# ECU.net
KiCad netlist of a schematic drawn in EAGLE
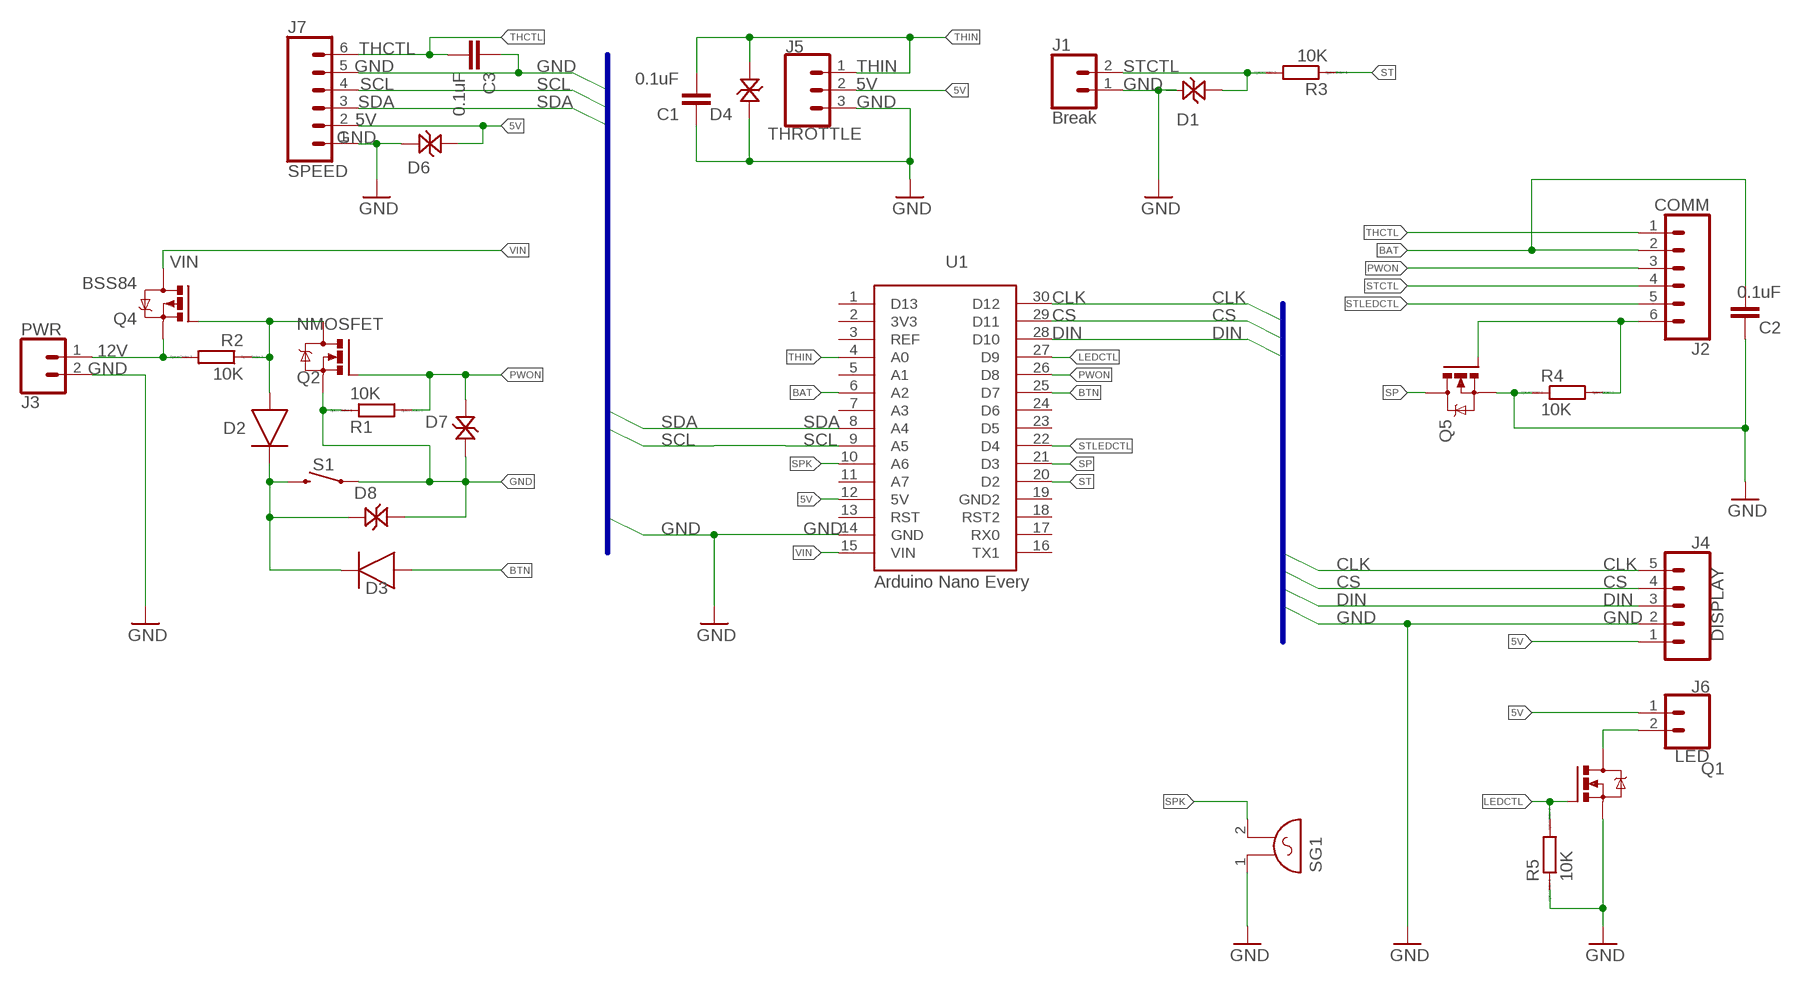
[diagram p0: schematic, sheet 1]

(export (version "E")
  (design (tool "Eeschema 10.0.6"))
  (components
    (comp (ref "C1")
      (value "0.1uF")
      (footprint "eagle-import:CAPC3216X135")
      (libsource (lib "eagle-import") (part "CCHIP-1206(3216-METRIC)_"))
    )
    (comp (ref "C2")
      (value "0.1uF")
      (footprint "eagle-import:CAPC3216X135")
      (libsource (lib "eagle-import") (part "CCHIP-1206(3216-METRIC)_"))
    )
    (comp (ref "C3")
      (value "0.1uF")
      (footprint "eagle-import:CAPC3216X135")
      (libsource (lib "eagle-import") (part "CCHIP-1206(3216-METRIC)_"))
    )
    (comp (ref "D1")
      (value "TVS_DIODESMA")
      (footprint "eagle-import:DIOM5027X220N")
      (libsource (lib "eagle-import") (part "TVS_DIODESMA"))
    )
    (comp (ref "D2")
      (value "DIODE_DO-215-AC")
      (footprint "eagle-import:SOD6126X290")
      (libsource (lib "eagle-import") (part "DIODEDO-215-AC_"))
    )
    (comp (ref "D3")
      (value "DIODE_DO-215-AC")
      (footprint "eagle-import:SOD6126X290")
      (libsource (lib "eagle-import") (part "DIODEDO-215-AC_"))
    )
    (comp (ref "D4")
      (value "TVS_DIODESMA")
      (footprint "eagle-import:DIOM5027X220N")
      (libsource (lib "eagle-import") (part "TVS_DIODESMA"))
    )
    (comp (ref "D6")
      (value "TVS_DIODESMA")
      (footprint "eagle-import:DIOM5027X220N")
      (libsource (lib "eagle-import") (part "TVS_DIODESMA"))
    )
    (comp (ref "D7")
      (value "TVS_DIODESMA")
      (footprint "eagle-import:DIOM5027X220N")
      (libsource (lib "eagle-import") (part "TVS_DIODESMA"))
    )
    (comp (ref "D8")
      (value "TVS_DIODESMA")
      (footprint "eagle-import:DIOM5027X220N")
      (libsource (lib "eagle-import") (part "TVS_DIODESMA"))
    )
    (comp (ref "J1")
      (value "Break")
      (footprint "eagle-import:1X02")
      (libsource (lib "eagle-import") (part "CONN_02"))
    )
    (comp (ref "J2")
      (value "COMM")
      (footprint "eagle-import:1X06")
      (libsource (lib "eagle-import") (part "CONN_06SILK_FEMALE_PTH"))
    )
    (comp (ref "J3")
      (value "PWR")
      (footprint "eagle-import:1X02")
      (libsource (lib "eagle-import") (part "CONN_02"))
    )
    (comp (ref "J4")
      (value "DISPLAY")
      (footprint "eagle-import:1X05")
      (libsource (lib "eagle-import") (part "CONN_05"))
    )
    (comp (ref "J5")
      (value "THROTTLE")
      (footprint "eagle-import:1X03")
      (libsource (lib "eagle-import") (part "CONN_03"))
    )
    (comp (ref "J6")
      (value "LED")
      (footprint "eagle-import:1X02")
      (libsource (lib "eagle-import") (part "CONN_02"))
    )
    (comp (ref "J7")
      (value "SPEED")
      (footprint "eagle-import:1X06")
      (libsource (lib "eagle-import") (part "CONN_06SILK_FEMALE_PTH"))
    )
    (comp (ref "Q1")
      (value "NMOSFET")
      (footprint "eagle-import:SOT23")
      (libsource (lib "eagle-import") (part "NMOSFETSOT23"))
    )
    (comp (ref "Q2")
      (value "NMOSFET")
      (footprint "eagle-import:SOT23")
      (libsource (lib "eagle-import") (part "NMOSFETSOT23"))
    )
    (comp (ref "Q4")
      (value "BSS84")
      (footprint "eagle-import:SOT23")
      (fields (field (name "MANUFACTURER") "ON Semiconductor"))
      (libsource (lib "eagle-import") (part "PMOSFET_BSS84"))
    )
    (comp (ref "Q5")
      (value "NMOSFET")
      (footprint "eagle-import:SOT23")
      (libsource (lib "eagle-import") (part "NMOSFETSOT23"))
    )
    (comp (ref "R1")
      (value "10K")
      (footprint "eagle-import:R1206")
      (libsource (lib "eagle-import") (part "RR1206"))
    )
    (comp (ref "R2")
      (value "10K")
      (footprint "eagle-import:R1206")
      (libsource (lib "eagle-import") (part "RR1206"))
    )
    (comp (ref "R3")
      (value "10K")
      (footprint "eagle-import:R1206")
      (libsource (lib "eagle-import") (part "RR1206"))
    )
    (comp (ref "R4")
      (value "10K")
      (footprint "eagle-import:R1206")
      (libsource (lib "eagle-import") (part "RR1206"))
    )
    (comp (ref "R5")
      (value "10K")
      (footprint "eagle-import:R1206")
      (libsource (lib "eagle-import") (part "RR1206"))
    )
    (comp (ref "S1")
      (value "MOMENTARY-SWITCH-SPST-PTH-6.0MM")
      (footprint "eagle-import:TACTILE_SWITCH_PTH_6.0MM")
      (libsource (lib "eagle-import") (part "MOMENTARY-SWITCH-SPST-PTH-6.0MM"))
    )
    (comp (ref "SG1")
      (value "F/HGP")
      (footprint "eagle-import:F_HGP")
      (libsource (lib "eagle-import") (part "F/HGP"))
    )
    (comp (ref "U1")
      (value "Arduino Nano Every")
      (footprint "eagle-import:SON254P1750X4300X120-30M")
      (libsource (lib "eagle-import") (part "ARDUINOARDUINO_NANO"))
    )
  )
  (nets
    (net (code "1") (name "/3V3") (class "Default")
      (node (ref "U1") (pin "2") (pinfunction "3V3_2") (pintype "power_in"))
    )
    (net (code "2") (name "/12V") (class "Default")
      (node (ref "J3") (pin "1") (pinfunction "1_1") (pintype "passive"))
      (node (ref "Q4") (pin "2") (pinfunction "S_2") (pintype "passive"))
      (node (ref "R2") (pin "2") (pinfunction "2_2") (pintype "passive"))
    )
    (net (code "3") (name "/CLK") (class "Default")
      (node (ref "J4") (pin "5") (pinfunction "5_5") (pintype "passive"))
      (node (ref "U1") (pin "30") (pinfunction "D12_30") (pintype "bidirectional"))
    )
    (net (code "4") (name "/CS") (class "Default")
      (node (ref "J4") (pin "4") (pinfunction "4_4") (pintype "passive"))
      (node (ref "U1") (pin "29") (pinfunction "D11_29") (pintype "bidirectional"))
    )
    (net (code "5") (name "/DIN") (class "Default")
      (node (ref "J4") (pin "3") (pinfunction "3_3") (pintype "passive"))
      (node (ref "U1") (pin "28") (pinfunction "D10_28") (pintype "bidirectional"))
    )
    (net (code "6") (name "/GND2") (class "Default")
      (node (ref "U1") (pin "19") (pinfunction "GND2_19") (pintype "power_in"))
    )
    (net (code "7") (name "/SCL") (class "Default")
      (node (ref "J7") (pin "4") (pinfunction "4_4") (pintype "passive"))
      (node (ref "U1") (pin "9") (pinfunction "A5_9") (pintype "bidirectional"))
    )
    (net (code "8") (name "/SDA") (class "Default")
      (node (ref "J7") (pin "3") (pinfunction "3_3") (pintype "passive"))
      (node (ref "U1") (pin "8") (pinfunction "A4_8") (pintype "bidirectional"))
    )
    (net (code "9") (name "5V") (class "Default")
      (node (ref "D6") (pin "1") (pinfunction "P$1_1") (pintype "bidirectional"))
      (node (ref "J4") (pin "1") (pinfunction "1_1") (pintype "passive"))
      (node (ref "J5") (pin "2") (pinfunction "2_2") (pintype "passive"))
      (node (ref "J6") (pin "1") (pinfunction "1_1") (pintype "passive"))
      (node (ref "J7") (pin "2") (pinfunction "2_2") (pintype "passive"))
      (node (ref "U1") (pin "12") (pinfunction "5V_12") (pintype "power_in"))
    )
    (net (code "10") (name "BAT") (class "Default")
      (node (ref "C2") (pin "1") (pinfunction "1_1") (pintype "passive"))
      (node (ref "J2") (pin "2") (pinfunction "2_2") (pintype "passive"))
      (node (ref "U1") (pin "6") (pinfunction "A2_6") (pintype "bidirectional"))
    )
    (net (code "11") (name "BTN") (class "Default")
      (node (ref "D3") (pin "2") (pinfunction "A_2") (pintype "passive"))
      (node (ref "U1") (pin "25") (pinfunction "D7_25") (pintype "bidirectional"))
    )
    (net (code "12") (name "GND") (class "Default")
      (node (ref "C1") (pin "1") (pinfunction "1_1") (pintype "passive"))
      (node (ref "C2") (pin "2") (pinfunction "2_2") (pintype "passive"))
      (node (ref "C3") (pin "2") (pinfunction "2_2") (pintype "passive"))
      (node (ref "D1") (pin "1") (pinfunction "P$1_1") (pintype "bidirectional"))
      (node (ref "D4") (pin "1") (pinfunction "P$1_1") (pintype "bidirectional"))
      (node (ref "D6") (pin "2") (pinfunction "P$2_2") (pintype "bidirectional"))
      (node (ref "D7") (pin "2") (pinfunction "P$2_2") (pintype "bidirectional"))
      (node (ref "D8") (pin "1") (pinfunction "P$1_1") (pintype "bidirectional"))
      (node (ref "J1") (pin "1") (pinfunction "1_1") (pintype "passive"))
      (node (ref "J3") (pin "2") (pinfunction "2_2") (pintype "passive"))
      (node (ref "J4") (pin "2") (pinfunction "2_2") (pintype "passive"))
      (node (ref "J5") (pin "3") (pinfunction "3_3") (pintype "passive"))
      (node (ref "J7") (pin "1") (pinfunction "1_1") (pintype "passive"))
      (node (ref "J7") (pin "5") (pinfunction "5_5") (pintype "passive"))
      (node (ref "Q1") (pin "2") (pinfunction "S_2") (pintype "passive"))
      (node (ref "Q2") (pin "2") (pinfunction "S_2") (pintype "passive"))
      (node (ref "Q5") (pin "2") (pinfunction "S_2") (pintype "passive"))
      (node (ref "R1") (pin "1") (pinfunction "1_1") (pintype "passive"))
      (node (ref "R4") (pin "1") (pinfunction "1_1") (pintype "passive"))
      (node (ref "R5") (pin "1") (pinfunction "1_1") (pintype "passive"))
      (node (ref "S1") (pin "1") (pinfunction "1_1") (pintype "passive"))
      (node (ref "S1") (pin "2") (pinfunction "1_2") (pintype "passive"))
      (node (ref "SG1") (pin "1") (pinfunction "1_1") (pintype "passive"))
      (node (ref "U1") (pin "14") (pinfunction "GND_14") (pintype "power_in"))
    )
    (net (code "13") (name "LEDCTL") (class "Default")
      (node (ref "Q1") (pin "1") (pinfunction "G_1") (pintype "passive"))
      (node (ref "R5") (pin "2") (pinfunction "2_2") (pintype "passive"))
      (node (ref "U1") (pin "27") (pinfunction "D9_27") (pintype "bidirectional"))
    )
    (net (code "14") (name "Net-(D2-A)") (class "Default")
      (node (ref "D2") (pin "2") (pinfunction "A_2") (pintype "passive"))
      (node (ref "Q2") (pin "3") (pinfunction "D_3") (pintype "passive"))
      (node (ref "Q4") (pin "1") (pinfunction "G_1") (pintype "passive"))
      (node (ref "R2") (pin "1") (pinfunction "1_1") (pintype "passive"))
    )
    (net (code "15") (name "Net-(D2-C)") (class "Default")
      (node (ref "D2") (pin "1") (pinfunction "C_1") (pintype "passive"))
      (node (ref "D3") (pin "1") (pinfunction "C_1") (pintype "passive"))
      (node (ref "D8") (pin "2") (pinfunction "P$2_2") (pintype "bidirectional"))
      (node (ref "S1") (pin "3") (pinfunction "2_3") (pintype "passive"))
      (node (ref "S1") (pin "4") (pinfunction "2_4") (pintype "passive"))
    )
    (net (code "16") (name "Net-(Q1-D)") (class "Default")
      (node (ref "J6") (pin "2") (pinfunction "2_2") (pintype "passive"))
      (node (ref "Q1") (pin "3") (pinfunction "D_3") (pintype "passive"))
    )
    (net (code "17") (name "Net-(Q5-G)") (class "Default")
      (node (ref "J2") (pin "6") (pinfunction "6_6") (pintype "passive"))
      (node (ref "Q5") (pin "1") (pinfunction "G_1") (pintype "passive"))
      (node (ref "R4") (pin "2") (pinfunction "2_2") (pintype "passive"))
    )
    (net (code "18") (name "PWON") (class "Default")
      (node (ref "D7") (pin "1") (pinfunction "P$1_1") (pintype "bidirectional"))
      (node (ref "J2") (pin "3") (pinfunction "3_3") (pintype "passive"))
      (node (ref "Q2") (pin "1") (pinfunction "G_1") (pintype "passive"))
      (node (ref "R1") (pin "2") (pinfunction "2_2") (pintype "passive"))
      (node (ref "U1") (pin "26") (pinfunction "D8_26") (pintype "bidirectional"))
    )
    (net (code "19") (name "SP") (class "Default")
      (node (ref "Q5") (pin "3") (pinfunction "D_3") (pintype "passive"))
      (node (ref "U1") (pin "21") (pinfunction "D3_21") (pintype "bidirectional"))
    )
    (net (code "20") (name "SPK") (class "Default")
      (node (ref "SG1") (pin "2") (pinfunction "2_2") (pintype "passive"))
      (node (ref "U1") (pin "10") (pinfunction "A6_10") (pintype "bidirectional"))
    )
    (net (code "21") (name "ST") (class "Default")
      (node (ref "R3") (pin "1") (pinfunction "1_1") (pintype "passive"))
      (node (ref "U1") (pin "20") (pinfunction "D2_20") (pintype "bidirectional"))
    )
    (net (code "22") (name "STCTL") (class "Default")
      (node (ref "D1") (pin "2") (pinfunction "P$2_2") (pintype "bidirectional"))
      (node (ref "J1") (pin "2") (pinfunction "2_2") (pintype "passive"))
      (node (ref "J2") (pin "4") (pinfunction "4_4") (pintype "passive"))
      (node (ref "R3") (pin "2") (pinfunction "2_2") (pintype "passive"))
    )
    (net (code "23") (name "STLEDCTL") (class "Default")
      (node (ref "J2") (pin "5") (pinfunction "5_5") (pintype "passive"))
      (node (ref "U1") (pin "22") (pinfunction "D4_22") (pintype "bidirectional"))
    )
    (net (code "24") (name "THCTL") (class "Default")
      (node (ref "C3") (pin "1") (pinfunction "1_1") (pintype "passive"))
      (node (ref "J2") (pin "1") (pinfunction "1_1") (pintype "passive"))
      (node (ref "J7") (pin "6") (pinfunction "6_6") (pintype "passive"))
    )
    (net (code "25") (name "THIN") (class "Default")
      (node (ref "C1") (pin "2") (pinfunction "2_2") (pintype "passive"))
      (node (ref "D4") (pin "2") (pinfunction "P$2_2") (pintype "bidirectional"))
      (node (ref "J5") (pin "1") (pinfunction "1_1") (pintype "passive"))
      (node (ref "U1") (pin "4") (pinfunction "A0_4") (pintype "bidirectional"))
    )
    (net (code "26") (name "VIN") (class "Default")
      (node (ref "Q4") (pin "3") (pinfunction "D_3") (pintype "passive"))
      (node (ref "U1") (pin "15") (pinfunction "VIN_15") (pintype "power_in"))
    )
    (net (code "27") (name "unconnected-(U1-A1-Pad5)") (class "Default")
      (node (ref "U1") (pin "5") (pinfunction "A1_5") (pintype "bidirectional"))
    )
    (net (code "28") (name "unconnected-(U1-A3-Pad7)") (class "Default")
      (node (ref "U1") (pin "7") (pinfunction "A3_7") (pintype "bidirectional"))
    )
    (net (code "29") (name "unconnected-(U1-A7-Pad11)") (class "Default")
      (node (ref "U1") (pin "11") (pinfunction "A7_11") (pintype "bidirectional"))
    )
    (net (code "30") (name "unconnected-(U1-D5-Pad23)") (class "Default")
      (node (ref "U1") (pin "23") (pinfunction "D5_23") (pintype "bidirectional"))
    )
    (net (code "31") (name "unconnected-(U1-D6-Pad24)") (class "Default")
      (node (ref "U1") (pin "24") (pinfunction "D6_24") (pintype "bidirectional"))
    )
    (net (code "32") (name "unconnected-(U1-D13-Pad1)") (class "Default")
      (node (ref "U1") (pin "1") (pinfunction "D13_1") (pintype "bidirectional"))
    )
    (net (code "33") (name "unconnected-(U1-REF-Pad3)") (class "Default")
      (node (ref "U1") (pin "3") (pinfunction "REF_3") (pintype "bidirectional"))
    )
    (net (code "34") (name "unconnected-(U1-RST-Pad13)") (class "Default")
      (node (ref "U1") (pin "13") (pinfunction "RST_13") (pintype "input"))
    )
    (net (code "35") (name "unconnected-(U1-RST2-Pad18)") (class "Default")
      (node (ref "U1") (pin "18") (pinfunction "RST2_18") (pintype "input"))
    )
    (net (code "36") (name "unconnected-(U1-RX0-Pad17)") (class "Default")
      (node (ref "U1") (pin "17") (pinfunction "RX0_17") (pintype "input"))
    )
    (net (code "37") (name "unconnected-(U1-TX1-Pad16)") (class "Default")
      (node (ref "U1") (pin "16") (pinfunction "TX1_16") (pintype "output"))
    )
  )
)
